# TDS_sensor_1.net
KiCad netlist of a schematic drawn in Altium Designer
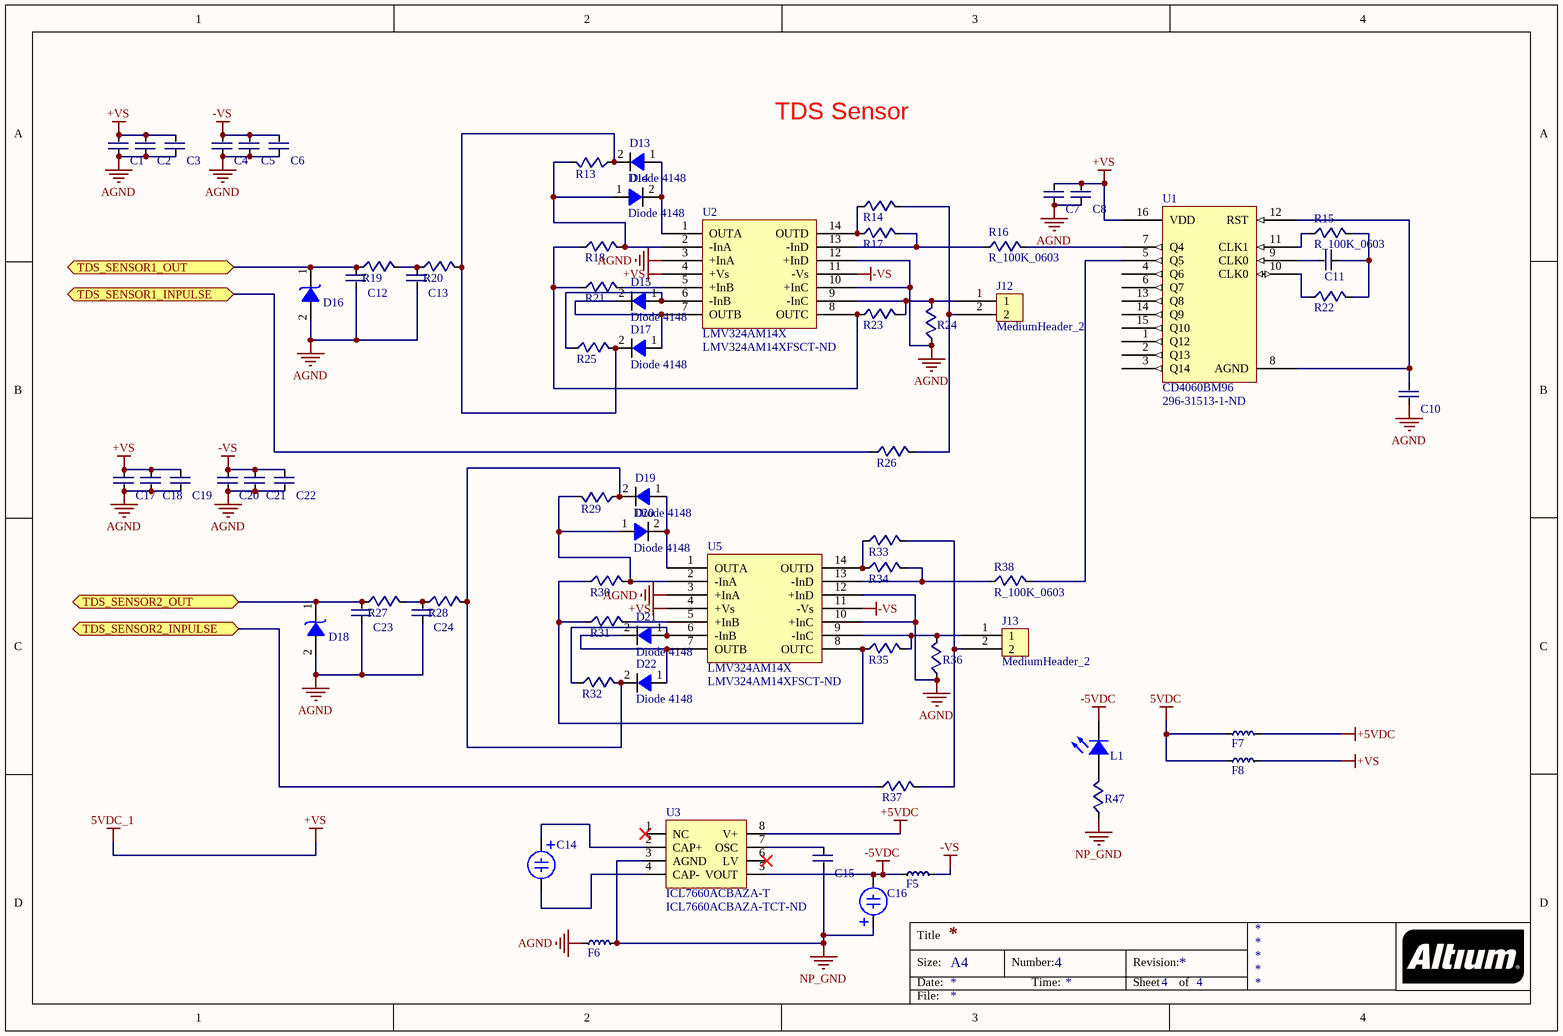
[diagram p0: TDS sensor 1.SchDoc]

(export (version "E")
  (design (tool "Eeschema 10.0.6"))
  (components
    (comp (ref "C1")
      (value "100n Cer")
      (footprint "CN-SMD-0805")
      (description "CAP CER 0.1UF 25V 10% X7R 0805")
      (libsource (lib "EngineersLife") (part "CAPC0805_104"))
    )
    (comp (ref "C2")
      (value "1n Cer")
      (footprint "CN-SMD-0805")
      (description "CAP CER 1000PF 50V 10% X7R 0805")
      (libsource (lib "EngineersLife") (part "CAPC0805_102"))
    )
    (comp (ref "C3")
      (value "10n Cer")
      (footprint "CN-SMD-0805")
      (description "CAP CER 10000PF 100V X7R 0805")
      (libsource (lib "EngineersLife") (part "CAPC0805_103"))
    )
    (comp (ref "C4")
      (value "100n Cer")
      (footprint "CN-SMD-0805")
      (description "CAP CER 0.1UF 25V 10% X7R 0805")
      (libsource (lib "EngineersLife") (part "CAPC0805_104"))
    )
    (comp (ref "C5")
      (value "1n Cer")
      (footprint "CN-SMD-0805")
      (description "CAP CER 1000PF 50V 10% X7R 0805")
      (libsource (lib "EngineersLife") (part "CAPC0805_102"))
    )
    (comp (ref "C6")
      (value "10n Cer")
      (footprint "CN-SMD-0805")
      (description "CAP CER 10000PF 100V X7R 0805")
      (libsource (lib "EngineersLife") (part "CAPC0805_103"))
    )
    (comp (ref "C7")
      (value "10n Cer")
      (footprint "CN-SMD-0805")
      (description "CAP CER 10000PF 100V X7R 0805")
      (libsource (lib "EngineersLife") (part "CAPC0805_103"))
    )
    (comp (ref "C8")
      (value "100n Cer")
      (footprint "CN-SMD-0805")
      (description "CAP CER 0.1UF 25V 10% X7R 0805")
      (libsource (lib "EngineersLife") (part "CAPC0805_104"))
    )
    (comp (ref "C10")
      (value "100n Cer")
      (footprint "CN-SMD-0805")
      (description "CAP CER 0.1UF 25V 10% X7R 0805")
      (libsource (lib "EngineersLife") (part "CAPC0805_104"))
    )
    (comp (ref "C11")
      (value "1n Cer")
      (footprint "CN-SMD-0805")
      (description "CAP CER 1000PF 50V 10% X7R 0805")
      (libsource (lib "EngineersLife") (part "CAPC0805_102"))
    )
    (comp (ref "C12")
      (value "10u Cer")
      (footprint "CN-SMD-0805")
      (description "CAP CER 10UF 6.3V 10% X7R 0805")
      (libsource (lib "EngineersLife") (part "CAPC0805_106"))
    )
    (comp (ref "C13")
      (value "10u Cer")
      (footprint "CN-SMD-0805")
      (description "CAP CER 10UF 6.3V 10% X7R 0805")
      (libsource (lib "EngineersLife") (part "CAPC0805_106"))
    )
    (comp (ref "C14")
      (value "CAP ALUM 100UF 25V 20% SMDL")
      (footprint "CAPALU_SM_5.3x5.3")
      (description "CAP ALUM 100UF 25V 20% SMD")
      (libsource (lib "EngineersLife") (part "CAPALU100U25V"))
    )
    (comp (ref "C15")
      (value "100n Cer")
      (footprint "CN-SMD-0805")
      (description "CAP CER 0.1UF 25V 10% X7R 0805")
      (libsource (lib "EngineersLife") (part "CAPC0805_104"))
    )
    (comp (ref "C16")
      (value "CAP ALUM 100UF 25V 20% SMDL")
      (footprint "CAPALU_SM_5.3x5.3")
      (description "CAP ALUM 100UF 25V 20% SMD")
      (libsource (lib "EngineersLife") (part "CAPALU100U25V"))
    )
    (comp (ref "C17")
      (value "100n Cer")
      (footprint "CN-SMD-0805")
      (description "CAP CER 0.1UF 25V 10% X7R 0805")
      (libsource (lib "EngineersLife") (part "CAPC0805_104"))
    )
    (comp (ref "C18")
      (value "1n Cer")
      (footprint "CN-SMD-0805")
      (description "CAP CER 1000PF 50V 10% X7R 0805")
      (libsource (lib "EngineersLife") (part "CAPC0805_102"))
    )
    (comp (ref "C19")
      (value "10n Cer")
      (footprint "CN-SMD-0805")
      (description "CAP CER 10000PF 100V X7R 0805")
      (libsource (lib "EngineersLife") (part "CAPC0805_103"))
    )
    (comp (ref "C20")
      (value "100n Cer")
      (footprint "CN-SMD-0805")
      (description "CAP CER 0.1UF 25V 10% X7R 0805")
      (libsource (lib "EngineersLife") (part "CAPC0805_104"))
    )
    (comp (ref "C21")
      (value "1n Cer")
      (footprint "CN-SMD-0805")
      (description "CAP CER 1000PF 50V 10% X7R 0805")
      (libsource (lib "EngineersLife") (part "CAPC0805_102"))
    )
    (comp (ref "C22")
      (value "10n Cer")
      (footprint "CN-SMD-0805")
      (description "CAP CER 10000PF 100V X7R 0805")
      (libsource (lib "EngineersLife") (part "CAPC0805_103"))
    )
    (comp (ref "C23")
      (value "10u Cer")
      (footprint "CN-SMD-0805")
      (description "CAP CER 10UF 6.3V 10% X7R 0805")
      (libsource (lib "EngineersLife") (part "CAPC0805_106"))
    )
    (comp (ref "C24")
      (value "10u Cer")
      (footprint "CN-SMD-0805")
      (description "CAP CER 10UF 6.3V 10% X7R 0805")
      (libsource (lib "EngineersLife") (part "CAPC0805_106"))
    )
    (comp (ref "D13")
      (value "Diode 4148")
      (footprint "CD3216-1206")
      (description "DIODE SWITCHING 75V 0.2A LLDS")
      (libsource (lib "EngineersLife") (part "Diode_4148"))
    )
    (comp (ref "D14")
      (value "Diode 4148")
      (footprint "CD3216-1206")
      (description "DIODE SWITCHING 75V 0.2A LLDS")
      (libsource (lib "EngineersLife") (part "Diode_4148"))
    )
    (comp (ref "D15")
      (value "Diode 4148")
      (footprint "CD3216-1206")
      (description "DIODE SWITCHING 75V 0.2A LLDS")
      (libsource (lib "EngineersLife") (part "Diode_4148"))
    )
    (comp (ref "D16")
      (value "Diode_SS34")
      (footprint "DO-214AB_MOD_EXT")
      (description "DIODE SCHOTTKY 40V 3A SMC")
      (libsource (lib "EngineersLife") (part "Diode_SS34"))
    )
    (comp (ref "D17")
      (value "Diode 4148")
      (footprint "CD3216-1206")
      (description "DIODE SWITCHING 75V 0.2A LLDS")
      (libsource (lib "EngineersLife") (part "Diode_4148"))
    )
    (comp (ref "D18")
      (value "Diode_SS34")
      (footprint "DO-214AB_MOD_EXT")
      (description "DIODE SCHOTTKY 40V 3A SMC")
      (libsource (lib "EngineersLife") (part "Diode_SS34"))
    )
    (comp (ref "D19")
      (value "Diode 4148")
      (footprint "CD3216-1206")
      (description "DIODE SWITCHING 75V 0.2A LLDS")
      (libsource (lib "EngineersLife") (part "Diode_4148"))
    )
    (comp (ref "D20")
      (value "Diode 4148")
      (footprint "CD3216-1206")
      (description "DIODE SWITCHING 75V 0.2A LLDS")
      (libsource (lib "EngineersLife") (part "Diode_4148"))
    )
    (comp (ref "D21")
      (value "Diode 4148")
      (footprint "CD3216-1206")
      (description "DIODE SWITCHING 75V 0.2A LLDS")
      (libsource (lib "EngineersLife") (part "Diode_4148"))
    )
    (comp (ref "D22")
      (value "Diode 4148")
      (footprint "CD3216-1206")
      (description "DIODE SWITCHING 75V 0.2A LLDS")
      (libsource (lib "EngineersLife") (part "Diode_4148"))
    )
    (comp (ref "F5")
      (value "FBFB0805")
      (footprint "RESC_0603")
      (description "FERRITE BEAD 1000 OHM 0603")
      (libsource (lib "EngineersLife") (part "FB0603_1000Ohm"))
    )
    (comp (ref "F6")
      (value "FBFB0805")
      (footprint "RESC_0603")
      (description "FERRITE BEAD 1000 OHM 0603")
      (libsource (lib "EngineersLife") (part "FB0603_1000Ohm"))
    )
    (comp (ref "F7")
      (value "FBFB0805")
      (footprint "RESC_0603")
      (description "FERRITE BEAD 1000 OHM 0603")
      (libsource (lib "EngineersLife") (part "FB0603_1000Ohm"))
    )
    (comp (ref "F8")
      (value "FBFB0805")
      (footprint "RESC_0603")
      (description "FERRITE BEAD 1000 OHM 0603")
      (libsource (lib "EngineersLife") (part "FB0603_1000Ohm"))
    )
    (comp (ref "J12")
      (value "MediumHeader_2")
      (footprint "Medium - Header 2")
      (libsource (lib "EngineersLife") (part "MediumHeader_2"))
    )
    (comp (ref "J13")
      (value "MediumHeader_2")
      (footprint "Medium - Header 2")
      (libsource (lib "EngineersLife") (part "MediumHeader_2"))
    )
    (comp (ref "L1")
      (value "LTST-C171KRKT")
      (footprint "LED_0805")
      (description "LED RED CLEAR 0805 SMD")
      (fields
        (field (name "MANUFACTURER") "Generic Components")
        (field (name "PUBLISHER") "Altium Hobart Technology Centre")
      )
      (libsource (lib "EngineersLife") (part "LED0805_RED"))
    )
    (comp (ref "R13")
      (value "R_10K_0603")
      (footprint "RES-SMD-0603")
      (description "RES 10.0K OHM 1/10W 1% 0603 SMD")
      (libsource (lib "EngineersLife") (part "RES0603_10K"))
    )
    (comp (ref "R14")
      (value "R_0R_0603")
      (footprint "RES-SMD-0603")
      (description "RES 0.0 OHM 1/10W JUMP 0603 SMD")
      (libsource (lib "EngineersLife") (part "RES0603_0R"))
    )
    (comp (ref "R15")
      (value "R_100K_0603")
      (footprint "RES-SMD-0603")
      (description "RES 100K OHM 1/10W 1% 0603 SMD")
      (libsource (lib "EngineersLife") (part "RES0603_100K"))
    )
    (comp (ref "R16")
      (value "R_100K_0603")
      (footprint "RES-SMD-0603")
      (description "RES 100K OHM 1/10W 1% 0603 SMD")
      (libsource (lib "EngineersLife") (part "RES0603_100K"))
    )
    (comp (ref "R17")
      (value "R_4K99_0603")
      (footprint "RES-SMD-0603")
      (description "RES 4.99K OHM 1/10W 1% 0603 SMD")
      (libsource (lib "EngineersLife") (part "RES0603_4K99"))
    )
    (comp (ref "R18")
      (value "R_10K_0603")
      (footprint "RES-SMD-0603")
      (description "RES 10.0K OHM 1/10W 1% 0603 SMD")
      (libsource (lib "EngineersLife") (part "RES0603_10K"))
    )
    (comp (ref "R19")
      (value "R_10K_0603")
      (footprint "RES-SMD-0603")
      (description "RES 10.0K OHM 1/10W 1% 0603 SMD")
      (libsource (lib "EngineersLife") (part "RES0603_10K"))
    )
    (comp (ref "R20")
      (value "R_10K_0603")
      (footprint "RES-SMD-0603")
      (description "RES 10.0K OHM 1/10W 1% 0603 SMD")
      (libsource (lib "EngineersLife") (part "RES0603_10K"))
    )
    (comp (ref "R21")
      (value "R_10K_0603")
      (footprint "RES-SMD-0603")
      (description "RES 10.0K OHM 1/10W 1% 0603 SMD")
      (libsource (lib "EngineersLife") (part "RES0603_10K"))
    )
    (comp (ref "R22")
      (value "R_10K_0603")
      (footprint "RES-SMD-0603")
      (description "RES 10.0K OHM 1/10W 1% 0603 SMD")
      (libsource (lib "EngineersLife") (part "RES0603_10K"))
    )
    (comp (ref "R23")
      (value "R_4K99_0603")
      (footprint "RES-SMD-0603")
      (description "RES 4.99K OHM 1/10W 1% 0603 SMD")
      (libsource (lib "EngineersLife") (part "RES0603_4K99"))
    )
    (comp (ref "R24")
      (value "R_1M_0603")
      (footprint "RES-SMD-0603")
      (description "RES 1M OHM 1/8W 1% 0603 SMD")
      (libsource (lib "EngineersLife") (part "RES0603_1M"))
    )
    (comp (ref "R25")
      (value "R_10K_0603")
      (footprint "RES-SMD-0603")
      (description "RES 10.0K OHM 1/10W 1% 0603 SMD")
      (libsource (lib "EngineersLife") (part "RES0603_10K"))
    )
    (comp (ref "R26")
      (value "R_0R_0603")
      (footprint "RES-SMD-0603")
      (description "RES 0.0 OHM 1/10W JUMP 0603 SMD")
      (libsource (lib "EngineersLife") (part "RES0603_0R"))
    )
    (comp (ref "R27")
      (value "R_10K_0603")
      (footprint "RES-SMD-0603")
      (description "RES 10.0K OHM 1/10W 1% 0603 SMD")
      (libsource (lib "EngineersLife") (part "RES0603_10K"))
    )
    (comp (ref "R28")
      (value "R_10K_0603")
      (footprint "RES-SMD-0603")
      (description "RES 10.0K OHM 1/10W 1% 0603 SMD")
      (libsource (lib "EngineersLife") (part "RES0603_10K"))
    )
    (comp (ref "R29")
      (value "R_10K_0603")
      (footprint "RES-SMD-0603")
      (description "RES 10.0K OHM 1/10W 1% 0603 SMD")
      (libsource (lib "EngineersLife") (part "RES0603_10K"))
    )
    (comp (ref "R30")
      (value "R_10K_0603")
      (footprint "RES-SMD-0603")
      (description "RES 10.0K OHM 1/10W 1% 0603 SMD")
      (libsource (lib "EngineersLife") (part "RES0603_10K"))
    )
    (comp (ref "R31")
      (value "R_10K_0603")
      (footprint "RES-SMD-0603")
      (description "RES 10.0K OHM 1/10W 1% 0603 SMD")
      (libsource (lib "EngineersLife") (part "RES0603_10K"))
    )
    (comp (ref "R32")
      (value "R_10K_0603")
      (footprint "RES-SMD-0603")
      (description "RES 10.0K OHM 1/10W 1% 0603 SMD")
      (libsource (lib "EngineersLife") (part "RES0603_10K"))
    )
    (comp (ref "R33")
      (value "R_0R_0603")
      (footprint "RES-SMD-0603")
      (description "RES 0.0 OHM 1/10W JUMP 0603 SMD")
      (libsource (lib "EngineersLife") (part "RES0603_0R"))
    )
    (comp (ref "R34")
      (value "R_4K99_0603")
      (footprint "RES-SMD-0603")
      (description "RES 4.99K OHM 1/10W 1% 0603 SMD")
      (libsource (lib "EngineersLife") (part "RES0603_4K99"))
    )
    (comp (ref "R35")
      (value "R_4K99_0603")
      (footprint "RES-SMD-0603")
      (description "RES 4.99K OHM 1/10W 1% 0603 SMD")
      (libsource (lib "EngineersLife") (part "RES0603_4K99"))
    )
    (comp (ref "R36")
      (value "R_1M_0603")
      (footprint "RES-SMD-0603")
      (description "RES 1M OHM 1/8W 1% 0603 SMD")
      (libsource (lib "EngineersLife") (part "RES0603_1M"))
    )
    (comp (ref "R37")
      (value "R_0R_0603")
      (footprint "RES-SMD-0603")
      (description "RES 0.0 OHM 1/10W JUMP 0603 SMD")
      (libsource (lib "EngineersLife") (part "RES0603_0R"))
    )
    (comp (ref "R38")
      (value "R_100K_0603")
      (footprint "RES-SMD-0603")
      (description "RES 100K OHM 1/10W 1% 0603 SMD")
      (libsource (lib "EngineersLife") (part "RES0603_100K"))
    )
    (comp (ref "R47")
      (value "R_560R_0603")
      (footprint "RES-SMD-0603")
      (description "RES 560 OHM 1/10W 0603 SMD")
      (libsource (lib "EngineersLife") (part "RES0603_560R"))
    )
    (comp (ref "U1")
      (value "CD4060BM96")
      (footprint "SOIC_16")
      (description "IC BINARY COUNTER/DIV/OSC 16SOIC")
      (fields (field (name "SUPPLIER PART NUMBER 1") "296-31513-1-ND"))
      (libsource (lib "EngineersLife") (part "CD4060BM"))
    )
    (comp (ref "U2")
      (value "LMV324AM14X")
      (footprint "SOIC-14")
      (description "IC OPAMP VFB 1.4MHZ RRO 14SOIC")
      (fields (field (name "SUPPLIER PART NUMBER 1") "LMV324AM14XFSCT-ND"))
      (libsource (lib "EngineersLife") (part "LMV324A"))
    )
    (comp (ref "U3")
      (value "ICL7660ACBAZA-T")
      (footprint "SOIC-8_MOD_24LC128")
      (description "IC REG SWTCHD CAP INV 45MA 8SOIC")
      (fields
        (field (name "SUPPLIER PART NUMBER 1") "ICL7660ACBAZA-TCT-ND")
        (field (name "CREATOR") "Nguyen Ba Bien")
      )
      (libsource (lib "EngineersLife") (part "ICL7660"))
    )
    (comp (ref "U5")
      (value "LMV324AM14X")
      (footprint "SOIC-14")
      (description "IC OPAMP VFB 1.4MHZ RRO 14SOIC")
      (fields (field (name "SUPPLIER PART NUMBER 1") "LMV324AM14XFSCT-ND"))
      (libsource (lib "EngineersLife") (part "LMV324A"))
    )
  )
  (nets
    (net (code "1") (name "+5VDC") (class "Default")
      (node (ref "F7") (pin "2") (pinfunction "2_2") (pintype "passive"))
      (node (ref "U3") (pin "8") (pinfunction "V+_8") (pintype "passive"))
    )
    (net (code "2") (name "+VS") (class "Default")
      (node (ref "C1") (pin "2") (pinfunction "2_2") (pintype "passive"))
      (node (ref "C17") (pin "2") (pinfunction "2_2") (pintype "passive"))
      (node (ref "C18") (pin "2") (pinfunction "2_2") (pintype "passive"))
      (node (ref "C19") (pin "2") (pinfunction "2_2") (pintype "passive"))
      (node (ref "C2") (pin "2") (pinfunction "2_2") (pintype "passive"))
      (node (ref "C3") (pin "2") (pinfunction "2_2") (pintype "passive"))
      (node (ref "C7") (pin "2") (pinfunction "2_2") (pintype "passive"))
      (node (ref "C8") (pin "2") (pinfunction "2_2") (pintype "passive"))
      (node (ref "F8") (pin "2") (pinfunction "2_2") (pintype "passive"))
      (node (ref "U1") (pin "16") (pinfunction "VDD_16") (pintype "power_in"))
      (node (ref "U2") (pin "4") (pinfunction "+Vs_4") (pintype "passive"))
      (node (ref "U5") (pin "4") (pinfunction "+Vs_4") (pintype "passive"))
    )
    (net (code "3") (name "-5VDC") (class "Default")
      (node (ref "C16") (pin "2") (pinfunction "2_2") (pintype "passive"))
      (node (ref "F5") (pin "1") (pinfunction "1_1") (pintype "passive"))
      (node (ref "L1") (pin "2") (pinfunction "K_2") (pintype "passive"))
      (node (ref "U3") (pin "5") (pinfunction "VOUT_5") (pintype "passive"))
    )
    (net (code "4") (name "-VS") (class "Default")
      (node (ref "C20") (pin "2") (pinfunction "2_2") (pintype "passive"))
      (node (ref "C21") (pin "2") (pinfunction "2_2") (pintype "passive"))
      (node (ref "C22") (pin "2") (pinfunction "2_2") (pintype "passive"))
      (node (ref "C4") (pin "2") (pinfunction "2_2") (pintype "passive"))
      (node (ref "C5") (pin "2") (pinfunction "2_2") (pintype "passive"))
      (node (ref "C6") (pin "2") (pinfunction "2_2") (pintype "passive"))
      (node (ref "F5") (pin "2") (pinfunction "2_2") (pintype "passive"))
      (node (ref "U2") (pin "11") (pinfunction "-Vs_11") (pintype "passive"))
      (node (ref "U5") (pin "11") (pinfunction "-Vs_11") (pintype "passive"))
    )
    (net (code "5") (name "/TDS_SENSOR1_INPULSE") (class "Default")
      (node (ref "R26") (pin "1") (pinfunction "1_1") (pintype "passive"))
    )
    (net (code "6") (name "/TDS_SENSOR1_OUT") (class "Default")
      (node (ref "C12") (pin "2") (pinfunction "2_2") (pintype "passive"))
      (node (ref "D16") (pin "1") (pinfunction "1_1") (pintype "passive"))
      (node (ref "R19") (pin "1") (pinfunction "1_1") (pintype "passive"))
    )
    (net (code "7") (name "/TDS_SENSOR2_INPULSE") (class "Default")
      (node (ref "R37") (pin "1") (pinfunction "1_1") (pintype "passive"))
    )
    (net (code "8") (name "/TDS_SENSOR2_OUT") (class "Default")
      (node (ref "C23") (pin "2") (pinfunction "2_2") (pintype "passive"))
      (node (ref "D18") (pin "1") (pinfunction "1_1") (pintype "passive"))
      (node (ref "R27") (pin "1") (pinfunction "1_1") (pintype "passive"))
    )
    (net (code "9") (name "5VDC") (class "Default")
      (node (ref "F7") (pin "1") (pinfunction "1_1") (pintype "passive"))
      (node (ref "F8") (pin "1") (pinfunction "1_1") (pintype "passive"))
    )
    (net (code "10") (name "AGND") (class "Default")
      (node (ref "C1") (pin "1") (pinfunction "1_1") (pintype "passive"))
      (node (ref "C10") (pin "1") (pinfunction "1_1") (pintype "passive"))
      (node (ref "C12") (pin "1") (pinfunction "1_1") (pintype "passive"))
      (node (ref "C13") (pin "1") (pinfunction "1_1") (pintype "passive"))
      (node (ref "C17") (pin "1") (pinfunction "1_1") (pintype "passive"))
      (node (ref "C18") (pin "1") (pinfunction "1_1") (pintype "passive"))
      (node (ref "C19") (pin "1") (pinfunction "1_1") (pintype "passive"))
      (node (ref "C2") (pin "1") (pinfunction "1_1") (pintype "passive"))
      (node (ref "C20") (pin "1") (pinfunction "1_1") (pintype "passive"))
      (node (ref "C21") (pin "1") (pinfunction "1_1") (pintype "passive"))
      (node (ref "C22") (pin "1") (pinfunction "1_1") (pintype "passive"))
      (node (ref "C23") (pin "1") (pinfunction "1_1") (pintype "passive"))
      (node (ref "C24") (pin "1") (pinfunction "1_1") (pintype "passive"))
      (node (ref "C3") (pin "1") (pinfunction "1_1") (pintype "passive"))
      (node (ref "C4") (pin "1") (pinfunction "1_1") (pintype "passive"))
      (node (ref "C5") (pin "1") (pinfunction "1_1") (pintype "passive"))
      (node (ref "C6") (pin "1") (pinfunction "1_1") (pintype "passive"))
      (node (ref "C7") (pin "1") (pinfunction "1_1") (pintype "passive"))
      (node (ref "C8") (pin "1") (pinfunction "1_1") (pintype "passive"))
      (node (ref "D16") (pin "2") (pinfunction "2_2") (pintype "passive"))
      (node (ref "D18") (pin "2") (pinfunction "2_2") (pintype "passive"))
      (node (ref "F6") (pin "1") (pinfunction "1_1") (pintype "passive"))
      (node (ref "R24") (pin "1") (pinfunction "1_1") (pintype "passive"))
      (node (ref "R36") (pin "1") (pinfunction "1_1") (pintype "passive"))
      (node (ref "U2") (pin "10") (pinfunction "+InC_10") (pintype "passive"))
      (node (ref "U2") (pin "12") (pinfunction "+InD_12") (pintype "passive"))
      (node (ref "U2") (pin "3") (pinfunction "+InA_3") (pintype "passive"))
      (node (ref "U5") (pin "10") (pinfunction "+InC_10") (pintype "passive"))
      (node (ref "U5") (pin "12") (pinfunction "+InD_12") (pintype "passive"))
      (node (ref "U5") (pin "3") (pinfunction "+InA_3") (pintype "passive"))
    )
    (net (code "11") (name "NP_GND") (class "Default")
      (node (ref "C15") (pin "1") (pinfunction "1_1") (pintype "passive"))
      (node (ref "C16") (pin "1") (pinfunction "1_1") (pintype "passive"))
      (node (ref "F6") (pin "2") (pinfunction "2_2") (pintype "passive"))
      (node (ref "R47") (pin "1") (pinfunction "1_1") (pintype "passive"))
      (node (ref "U3") (pin "3") (pinfunction "AGND_3") (pintype "passive"))
    )
    (net (code "12") (name "Net-(C11-Pad1)") (class "Default")
      (node (ref "C11") (pin "1") (pinfunction "1_1") (pintype "passive"))
      (node (ref "U1") (pin "9") (pinfunction "CLK0_9") (pintype "input"))
    )
    (net (code "13") (name "Net-(C11-Pad2)") (class "Default")
      (node (ref "C11") (pin "2") (pinfunction "2_2") (pintype "passive"))
      (node (ref "R15") (pin "2") (pinfunction "2_2") (pintype "passive"))
      (node (ref "R22") (pin "2") (pinfunction "2_2") (pintype "passive"))
    )
    (net (code "14") (name "Net-(C13-Pad2)") (class "Default")
      (node (ref "C13") (pin "2") (pinfunction "2_2") (pintype "passive"))
      (node (ref "R19") (pin "2") (pinfunction "2_2") (pintype "passive"))
      (node (ref "R20") (pin "1") (pinfunction "1_1") (pintype "passive"))
    )
    (net (code "15") (name "Net-(C24-Pad2)") (class "Default")
      (node (ref "C24") (pin "2") (pinfunction "2_2") (pintype "passive"))
      (node (ref "R27") (pin "2") (pinfunction "2_2") (pintype "passive"))
      (node (ref "R28") (pin "1") (pinfunction "1_1") (pintype "passive"))
    )
    (net (code "16") (name "Net-(D13-3)") (class "Default")
      (node (ref "D13") (pin "1") (pinfunction "3_1") (pintype "passive"))
      (node (ref "D14") (pin "2") (pinfunction "4_2") (pintype "passive"))
      (node (ref "U2") (pin "1") (pinfunction "OUTA_1") (pintype "passive"))
    )
    (net (code "17") (name "Net-(D13-4)") (class "Default")
      (node (ref "D13") (pin "2") (pinfunction "4_2") (pintype "passive"))
      (node (ref "D17") (pin "2") (pinfunction "4_2") (pintype "passive"))
      (node (ref "R13") (pin "1") (pinfunction "1_1") (pintype "passive"))
      (node (ref "R20") (pin "2") (pinfunction "2_2") (pintype "passive"))
      (node (ref "R25") (pin "2") (pinfunction "2_2") (pintype "passive"))
    )
    (net (code "18") (name "Net-(D14-3)") (class "Default")
      (node (ref "D14") (pin "1") (pinfunction "3_1") (pintype "passive"))
      (node (ref "R13") (pin "2") (pinfunction "2_2") (pintype "passive"))
      (node (ref "R18") (pin "2") (pinfunction "2_2") (pintype "passive"))
      (node (ref "U2") (pin "2") (pinfunction "-InA_2") (pintype "passive"))
    )
    (net (code "19") (name "Net-(D15-3)") (class "Default")
      (node (ref "D15") (pin "1") (pinfunction "3_1") (pintype "passive"))
      (node (ref "R25") (pin "1") (pinfunction "1_1") (pintype "passive"))
      (node (ref "U2") (pin "6") (pinfunction "-InB_6") (pintype "passive"))
    )
    (net (code "20") (name "Net-(D15-4)") (class "Default")
      (node (ref "D15") (pin "2") (pinfunction "4_2") (pintype "passive"))
      (node (ref "D17") (pin "1") (pinfunction "3_1") (pintype "passive"))
      (node (ref "U2") (pin "7") (pinfunction "OUTB_7") (pintype "passive"))
    )
    (net (code "21") (name "Net-(D19-3)") (class "Default")
      (node (ref "D19") (pin "1") (pinfunction "3_1") (pintype "passive"))
      (node (ref "D20") (pin "2") (pinfunction "4_2") (pintype "passive"))
      (node (ref "U5") (pin "1") (pinfunction "OUTA_1") (pintype "passive"))
    )
    (net (code "22") (name "Net-(D19-4)") (class "Default")
      (node (ref "D19") (pin "2") (pinfunction "4_2") (pintype "passive"))
      (node (ref "D22") (pin "2") (pinfunction "4_2") (pintype "passive"))
      (node (ref "R28") (pin "2") (pinfunction "2_2") (pintype "passive"))
      (node (ref "R29") (pin "1") (pinfunction "1_1") (pintype "passive"))
      (node (ref "R32") (pin "2") (pinfunction "2_2") (pintype "passive"))
    )
    (net (code "23") (name "Net-(D20-3)") (class "Default")
      (node (ref "D20") (pin "1") (pinfunction "3_1") (pintype "passive"))
      (node (ref "R29") (pin "2") (pinfunction "2_2") (pintype "passive"))
      (node (ref "R30") (pin "2") (pinfunction "2_2") (pintype "passive"))
      (node (ref "U5") (pin "2") (pinfunction "-InA_2") (pintype "passive"))
    )
    (net (code "24") (name "Net-(D21-3)") (class "Default")
      (node (ref "D21") (pin "1") (pinfunction "3_1") (pintype "passive"))
      (node (ref "R32") (pin "1") (pinfunction "1_1") (pintype "passive"))
      (node (ref "U5") (pin "6") (pinfunction "-InB_6") (pintype "passive"))
    )
    (net (code "25") (name "Net-(D21-4)") (class "Default")
      (node (ref "D21") (pin "2") (pinfunction "4_2") (pintype "passive"))
      (node (ref "D22") (pin "1") (pinfunction "3_1") (pintype "passive"))
      (node (ref "U5") (pin "7") (pinfunction "OUTB_7") (pintype "passive"))
    )
    (net (code "26") (name "Net-(J12-Pad2)") (class "Default")
      (node (ref "J12") (pin "2") (pinfunction "2_2") (pintype "passive"))
      (node (ref "R14") (pin "2") (pinfunction "2_2") (pintype "passive"))
      (node (ref "R26") (pin "2") (pinfunction "2_2") (pintype "passive"))
    )
    (net (code "27") (name "Net-(J13-Pad2)") (class "Default")
      (node (ref "J13") (pin "2") (pinfunction "2_2") (pintype "passive"))
      (node (ref "R33") (pin "2") (pinfunction "2_2") (pintype "passive"))
      (node (ref "R37") (pin "2") (pinfunction "2_2") (pintype "passive"))
    )
    (net (code "28") (name "Net-(L1-A)") (class "Default")
      (node (ref "L1") (pin "1") (pinfunction "A_1") (pintype "passive"))
      (node (ref "R47") (pin "2") (pinfunction "2_2") (pintype "passive"))
    )
    (net (code "29") (name "Net-(R22-Pad1)") (class "Default")
      (node (ref "R22") (pin "1") (pinfunction "1_1") (pintype "passive"))
      (node (ref "U1") (pin "10") (pinfunction "CLK0_10") (pintype "bidirectional"))
    )
    (net (code "30") (name "Net-(U1-AGND)") (class "Default")
      (node (ref "C10") (pin "2") (pinfunction "2_2") (pintype "passive"))
      (node (ref "U1") (pin "12") (pinfunction "RST_12") (pintype "input"))
      (node (ref "U1") (pin "8") (pinfunction "AGND_8") (pintype "power_in"))
    )
    (net (code "31") (name "Net-(U1-CLK1)") (class "Default")
      (node (ref "R15") (pin "1") (pinfunction "1_1") (pintype "passive"))
      (node (ref "U1") (pin "11") (pinfunction "CLK1_11") (pintype "input"))
    )
    (net (code "32") (name "Net-(U1-Q4)") (class "Default")
      (node (ref "R16") (pin "2") (pinfunction "2_2") (pintype "passive"))
      (node (ref "U1") (pin "7") (pinfunction "Q4_7") (pintype "output"))
    )
    (net (code "33") (name "Net-(U1-Q5)") (class "Default")
      (node (ref "R38") (pin "2") (pinfunction "2_2") (pintype "passive"))
      (node (ref "U1") (pin "5") (pinfunction "Q5_5") (pintype "output"))
    )
    (net (code "34") (name "Net-(U2-+InB)") (class "Default")
      (node (ref "R21") (pin "2") (pinfunction "2_2") (pintype "passive"))
      (node (ref "U2") (pin "5") (pinfunction "+InB_5") (pintype "passive"))
    )
    (net (code "35") (name "Net-(U2--InC)") (class "Default")
      (node (ref "J12") (pin "1") (pinfunction "1_1") (pintype "passive"))
      (node (ref "R23") (pin "2") (pinfunction "2_2") (pintype "passive"))
      (node (ref "R24") (pin "2") (pinfunction "2_2") (pintype "passive"))
      (node (ref "U2") (pin "9") (pinfunction "-InC_9") (pintype "passive"))
    )
    (net (code "36") (name "Net-(U2--InD)") (class "Default")
      (node (ref "R16") (pin "1") (pinfunction "1_1") (pintype "passive"))
      (node (ref "R17") (pin "2") (pinfunction "2_2") (pintype "passive"))
      (node (ref "U2") (pin "13") (pinfunction "-InD_13") (pintype "passive"))
    )
    (net (code "37") (name "Net-(U2-OUTC)") (class "Default")
      (node (ref "R18") (pin "1") (pinfunction "1_1") (pintype "passive"))
      (node (ref "R21") (pin "1") (pinfunction "1_1") (pintype "passive"))
      (node (ref "R23") (pin "1") (pinfunction "1_1") (pintype "passive"))
      (node (ref "U2") (pin "8") (pinfunction "OUTC_8") (pintype "passive"))
    )
    (net (code "38") (name "Net-(U2-OUTD)") (class "Default")
      (node (ref "R14") (pin "1") (pinfunction "1_1") (pintype "passive"))
      (node (ref "R17") (pin "1") (pinfunction "1_1") (pintype "passive"))
      (node (ref "U2") (pin "14") (pinfunction "OUTD_14") (pintype "passive"))
    )
    (net (code "39") (name "Net-(U3-CAP+)") (class "Default")
      (node (ref "C14") (pin "1") (pinfunction "1_1") (pintype "passive"))
      (node (ref "U3") (pin "2") (pinfunction "CAP+_2") (pintype "passive"))
    )
    (net (code "40") (name "Net-(U3-CAP-)") (class "Default")
      (node (ref "C14") (pin "2") (pinfunction "2_2") (pintype "passive"))
      (node (ref "U3") (pin "4") (pinfunction "CAP-_4") (pintype "passive"))
    )
    (net (code "41") (name "Net-(U3-OSC)") (class "Default")
      (node (ref "C15") (pin "2") (pinfunction "2_2") (pintype "passive"))
      (node (ref "U3") (pin "7") (pinfunction "OSC_7") (pintype "passive"))
    )
    (net (code "42") (name "Net-(U5-+InB)") (class "Default")
      (node (ref "R31") (pin "2") (pinfunction "2_2") (pintype "passive"))
      (node (ref "U5") (pin "5") (pinfunction "+InB_5") (pintype "passive"))
    )
    (net (code "43") (name "Net-(U5--InC)") (class "Default")
      (node (ref "J13") (pin "1") (pinfunction "1_1") (pintype "passive"))
      (node (ref "R35") (pin "2") (pinfunction "2_2") (pintype "passive"))
      (node (ref "R36") (pin "2") (pinfunction "2_2") (pintype "passive"))
      (node (ref "U5") (pin "9") (pinfunction "-InC_9") (pintype "passive"))
    )
    (net (code "44") (name "Net-(U5--InD)") (class "Default")
      (node (ref "R34") (pin "2") (pinfunction "2_2") (pintype "passive"))
      (node (ref "R38") (pin "1") (pinfunction "1_1") (pintype "passive"))
      (node (ref "U5") (pin "13") (pinfunction "-InD_13") (pintype "passive"))
    )
    (net (code "45") (name "Net-(U5-OUTC)") (class "Default")
      (node (ref "R30") (pin "1") (pinfunction "1_1") (pintype "passive"))
      (node (ref "R31") (pin "1") (pinfunction "1_1") (pintype "passive"))
      (node (ref "R35") (pin "1") (pinfunction "1_1") (pintype "passive"))
      (node (ref "U5") (pin "8") (pinfunction "OUTC_8") (pintype "passive"))
    )
    (net (code "46") (name "Net-(U5-OUTD)") (class "Default")
      (node (ref "R33") (pin "1") (pinfunction "1_1") (pintype "passive"))
      (node (ref "R34") (pin "1") (pinfunction "1_1") (pintype "passive"))
      (node (ref "U5") (pin "14") (pinfunction "OUTD_14") (pintype "passive"))
    )
    (net (code "47") (name "unconnected-(U1-Q6-Pad4)") (class "Default")
      (node (ref "U1") (pin "4") (pinfunction "Q6_4") (pintype "output"))
    )
    (net (code "48") (name "unconnected-(U1-Q7-Pad6)") (class "Default")
      (node (ref "U1") (pin "6") (pinfunction "Q7_6") (pintype "output"))
    )
    (net (code "49") (name "unconnected-(U1-Q8-Pad13)") (class "Default")
      (node (ref "U1") (pin "13") (pinfunction "Q8_13") (pintype "output"))
    )
    (net (code "50") (name "unconnected-(U1-Q9-Pad14)") (class "Default")
      (node (ref "U1") (pin "14") (pinfunction "Q9_14") (pintype "output"))
    )
    (net (code "51") (name "unconnected-(U1-Q10-Pad15)") (class "Default")
      (node (ref "U1") (pin "15") (pinfunction "Q10_15") (pintype "output"))
    )
    (net (code "52") (name "unconnected-(U1-Q12-Pad1)") (class "Default")
      (node (ref "U1") (pin "1") (pinfunction "Q12_1") (pintype "output"))
    )
    (net (code "53") (name "unconnected-(U1-Q13-Pad2)") (class "Default")
      (node (ref "U1") (pin "2") (pinfunction "Q13_2") (pintype "output"))
    )
    (net (code "54") (name "unconnected-(U1-Q14-Pad3)") (class "Default")
      (node (ref "U1") (pin "3") (pinfunction "Q14_3") (pintype "output"))
    )
    (net (code "55") (name "unconnected-(U3-LV-Pad6)") (class "Default")
      (node (ref "U3") (pin "6") (pinfunction "LV_6") (pintype "passive+no_connect"))
    )
    (net (code "56") (name "unconnected-(U3-NC-Pad1)") (class "Default")
      (node (ref "U3") (pin "1") (pinfunction "NC_1") (pintype "passive+no_connect"))
    )
  )
)
